# ESP32.net
KiCad netlist of a schematic drawn in EAGLE
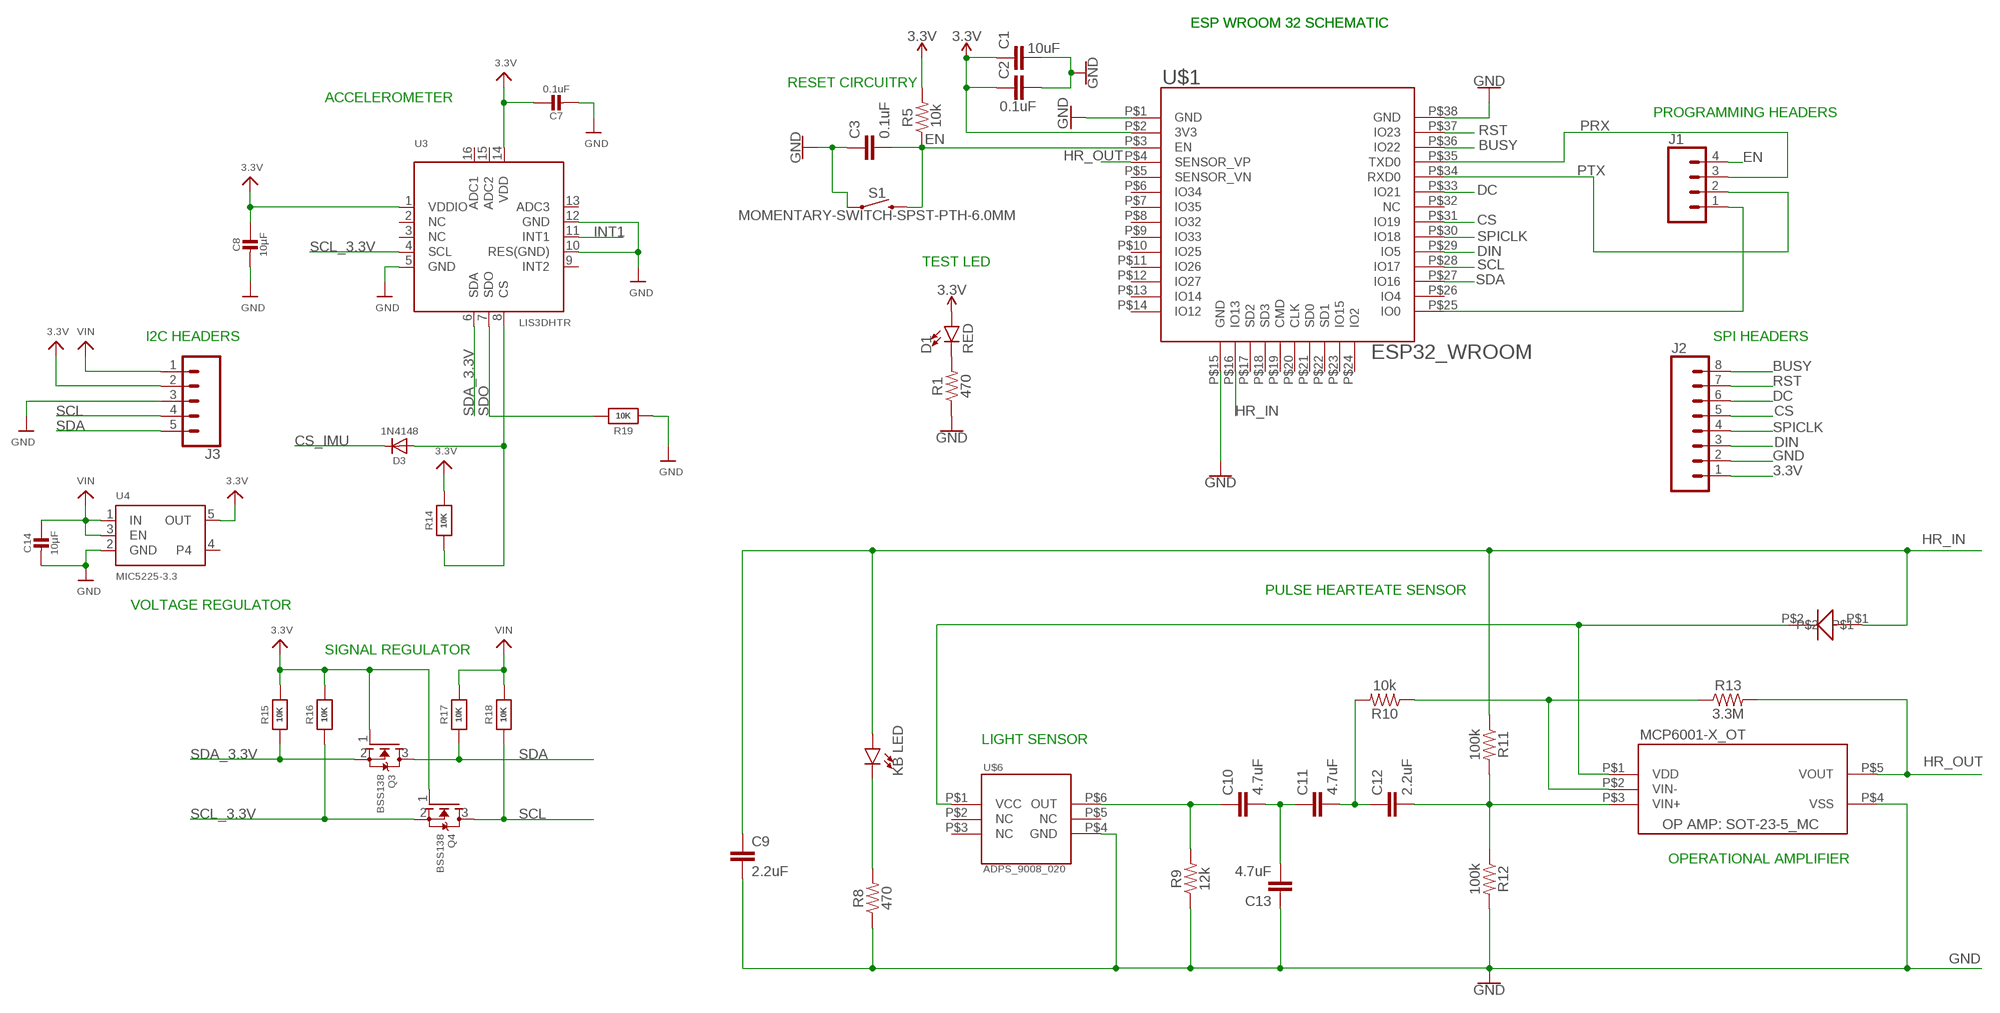
[diagram p0: schematic, sheet 1]

(export (version "E")
  (design (tool "Eeschema 10.0.6"))
  (components
    (comp (ref "C1")
      (value "10uF")
      (footprint "eagle-import:0603")
      (libsource (lib "eagle-import") (part "10UF-0603-6.3V-20%"))
    )
    (comp (ref "C2")
      (value "0.1uF")
      (footprint "eagle-import:0603")
      (libsource (lib "eagle-import") (part "0.1UF-0603-25V-(+80/-20%)"))
    )
    (comp (ref "C3")
      (value "0.1uF")
      (footprint "eagle-import:0603")
      (libsource (lib "eagle-import") (part "0.1UF-0603-25V-(+80/-20%)"))
    )
    (comp (ref "C7")
      (value "0.1uF")
      (footprint "eagle-import:_0603MP")
      (libsource (lib "eagle-import") (part "CAP_CERAMIC_0603MP"))
    )
    (comp (ref "C8")
      (value "10µF")
      (footprint "eagle-import:_0603")
      (libsource (lib "eagle-import") (part "CAP_CERAMIC_0603"))
    )
    (comp (ref "C9")
      (value "2.2uF")
      (footprint "eagle-import:0603")
      (libsource (lib "eagle-import") (part "2.2UF-0603-10V-20%"))
    )
    (comp (ref "C10")
      (value "4.7uF")
      (footprint "eagle-import:0603")
      (libsource (lib "eagle-import") (part "4.7UF0603"))
    )
    (comp (ref "C11")
      (value "4.7uF")
      (footprint "eagle-import:0603")
      (libsource (lib "eagle-import") (part "4.7UF0603"))
    )
    (comp (ref "C12")
      (value "2.2uF")
      (footprint "eagle-import:0603")
      (libsource (lib "eagle-import") (part "2.2UF-0603-10V-20%"))
    )
    (comp (ref "C13")
      (value "4.7uF")
      (footprint "eagle-import:0603")
      (libsource (lib "eagle-import") (part "4.7UF0603"))
    )
    (comp (ref "C14")
      (value "10µF")
      (footprint "eagle-import:_0603")
      (libsource (lib "eagle-import") (part "CAP_CERAMIC_0603"))
    )
    (comp (ref "D1")
      (value "RED")
      (footprint "eagle-import:LED-0603")
      (libsource (lib "eagle-import") (part "LED-RED0603"))
    )
    (comp (ref "D3")
      (value "1N4148")
      (footprint "eagle-import:SOD-323")
      (libsource (lib "eagle-import") (part "DIODESOD-323"))
    )
    (comp (ref "J1")
      (value "CONN_04")
      (footprint "eagle-import:1X04")
      (libsource (lib "eagle-import") (part "CONN_04"))
    )
    (comp (ref "J2")
      (value "CONN_08\"")
      (footprint "eagle-import:1X08")
      (libsource (lib "eagle-import") (part "CONN_08{dblquote}"))
    )
    (comp (ref "J3")
      (value "CONN_05")
      (footprint "eagle-import:1X05")
      (libsource (lib "eagle-import") (part "CONN_05"))
    )
    (comp (ref "Q3")
      (value "BSS138")
      (footprint "eagle-import:SOT23-WIDE")
      (libsource (lib "eagle-import") (part "MOSFET-NWIDE"))
    )
    (comp (ref "Q4")
      (value "BSS138")
      (footprint "eagle-import:SOT23-WIDE")
      (libsource (lib "eagle-import") (part "MOSFET-NWIDE"))
    )
    (comp (ref "R1")
      (value "470")
      (footprint "eagle-import:0603")
      (libsource (lib "eagle-import") (part "RESISTOR0603"))
    )
    (comp (ref "R5")
      (value "10k")
      (footprint "eagle-import:0603")
      (libsource (lib "eagle-import") (part "RESISTOR0603"))
    )
    (comp (ref "R8")
      (value "470")
      (footprint "eagle-import:0603")
      (libsource (lib "eagle-import") (part "RESISTOR0603"))
    )
    (comp (ref "R9")
      (value "12k")
      (footprint "eagle-import:0603")
      (libsource (lib "eagle-import") (part "RESISTOR0603"))
    )
    (comp (ref "R10")
      (value "10k")
      (footprint "eagle-import:0603")
      (libsource (lib "eagle-import") (part "RESISTOR0603"))
    )
    (comp (ref "R11")
      (value "100k")
      (footprint "eagle-import:0603")
      (libsource (lib "eagle-import") (part "RESISTOR0603"))
    )
    (comp (ref "R12")
      (value "100k")
      (footprint "eagle-import:0603")
      (libsource (lib "eagle-import") (part "RESISTOR0603"))
    )
    (comp (ref "R13")
      (value "3.3M")
      (footprint "eagle-import:0603")
      (libsource (lib "eagle-import") (part "RESISTOR0603"))
    )
    (comp (ref "R14")
      (value "10K")
      (footprint "eagle-import:_0603")
      (libsource (lib "eagle-import") (part "RESISTOR_0603"))
    )
    (comp (ref "R15")
      (value "10K")
      (footprint "eagle-import:_0603")
      (libsource (lib "eagle-import") (part "RESISTOR_0603"))
    )
    (comp (ref "R16")
      (value "10K")
      (footprint "eagle-import:_0603")
      (libsource (lib "eagle-import") (part "RESISTOR_0603"))
    )
    (comp (ref "R17")
      (value "10K")
      (footprint "eagle-import:_0603")
      (libsource (lib "eagle-import") (part "RESISTOR_0603"))
    )
    (comp (ref "R18")
      (value "10K")
      (footprint "eagle-import:_0603")
      (libsource (lib "eagle-import") (part "RESISTOR_0603"))
    )
    (comp (ref "R19")
      (value "10K")
      (footprint "eagle-import:_0603")
      (libsource (lib "eagle-import") (part "RESISTOR_0603"))
    )
    (comp (ref "S1")
      (value "MOMENTARY-SWITCH-SPST-PTH-6.0MM")
      (footprint "eagle-import:TACTILE_SWITCH_PTH_6.0MM")
      (libsource (lib "eagle-import") (part "MOMENTARY-SWITCH-SPST-PTH-6.0MM"))
    )
    (comp (ref "U$1")
      (value "ESP32_WROOM")
      (footprint "eagle-import:ESP32_FP")
      (libsource (lib "eagle-import") (part "ESP32_WROOM"))
    )
    (comp (ref "U$5")
      (value "MCP6001-X_SOT-23-5")
      (footprint "eagle-import:SOT-23-5")
      (libsource (lib "eagle-import") (part "MCP6001-X_SOT-23-5"))
    )
    (comp (ref "U$6")
      (value "ADPS_9008_020")
      (footprint "eagle-import:ADPS_FP")
      (libsource (lib "eagle-import") (part "ADPS_9008_020"))
    )
    (comp (ref "U$7")
      (value "KB_REVMNT_LED")
      (footprint "eagle-import:REVMNT_LED_FP")
      (libsource (lib "eagle-import") (part "KB_REVMNT_LED"))
    )
    (comp (ref "U$8")
      (value "DI0603")
      (footprint "eagle-import:DIODE0603")
      (libsource (lib "eagle-import") (part "DI0603"))
    )
    (comp (ref "U3")
      (value "LIS3DHTR")
      (footprint "eagle-import:LGA16_3X3MM")
      (libsource (lib "eagle-import") (part "ACCEL_LIS3DHTR"))
    )
    (comp (ref "U4")
      (value "MIC5225-3.3")
      (footprint "eagle-import:SOT23-5")
      (libsource (lib "eagle-import") (part "VREG_SOT23-5"))
    )
  )
  (nets
    (net (code "1") (name "/BUSY") (class "Default")
      (node (ref "J2") (pin "8") (pinfunction "8_8") (pintype "passive"))
      (node (ref "U$1") (pin "P$36") (pinfunction "IO22_P$36") (pintype "bidirectional"))
    )
    (net (code "2") (name "/CS") (class "Default")
      (node (ref "J2") (pin "5") (pinfunction "5_5") (pintype "passive"))
      (node (ref "U$1") (pin "P$31") (pinfunction "IO19_P$31") (pintype "bidirectional"))
    )
    (net (code "3") (name "/CS_IMU") (class "Default")
      (node (ref "D3") (pin "C") (pinfunction "C_C") (pintype "passive"))
    )
    (net (code "4") (name "/DC") (class "Default")
      (node (ref "J2") (pin "6") (pinfunction "6_6") (pintype "passive"))
      (node (ref "U$1") (pin "P$33") (pinfunction "IO21_P$33") (pintype "bidirectional"))
    )
    (net (code "5") (name "/DIN") (class "Default")
      (node (ref "J2") (pin "3") (pinfunction "3_3") (pintype "passive"))
      (node (ref "U$1") (pin "P$29") (pinfunction "IO5_P$29") (pintype "bidirectional"))
    )
    (net (code "6") (name "/EN") (class "Default")
      (node (ref "C3") (pin "2") (pinfunction "2_2") (pintype "passive"))
      (node (ref "J1") (pin "4") (pinfunction "4_4") (pintype "passive"))
      (node (ref "R5") (pin "1") (pinfunction "1_1") (pintype "passive"))
      (node (ref "S1") (pin "3") (pinfunction "2_3") (pintype "passive"))
      (node (ref "U$1") (pin "P$3") (pinfunction "EN_P$3") (pintype "input"))
    )
    (net (code "7") (name "/HR_IN") (class "Default")
      (node (ref "C9") (pin "1") (pinfunction "1_1") (pintype "passive"))
      (node (ref "R11") (pin "1") (pinfunction "1_1") (pintype "passive"))
      (node (ref "U$1") (pin "P$16") (pinfunction "IO13_P$16") (pintype "bidirectional"))
      (node (ref "U$7") (pin "P$1") (pinfunction "A_P$1") (pintype "passive"))
      (node (ref "U$8") (pin "P$1") (pinfunction "P$2_P$1") (pintype "bidirectional"))
    )
    (net (code "8") (name "/HR_OUT") (class "Default")
      (node (ref "R13") (pin "2") (pinfunction "2_2") (pintype "passive"))
      (node (ref "U$1") (pin "P$4") (pinfunction "SENSOR_VP_P$4") (pintype "input"))
      (node (ref "U$5") (pin "P$5") (pinfunction "VOUT_P$5") (pintype "output"))
    )
    (net (code "9") (name "/INT1") (class "Default")
      (node (ref "U3") (pin "11") (pinfunction "INT1_11") (pintype "output"))
    )
    (net (code "10") (name "/PRX") (class "Default")
      (node (ref "J1") (pin "3") (pinfunction "3_3") (pintype "passive"))
      (node (ref "U$1") (pin "P$35") (pinfunction "TXD0_P$35") (pintype "bidirectional"))
    )
    (net (code "11") (name "/PTX") (class "Default")
      (node (ref "J1") (pin "2") (pinfunction "2_2") (pintype "passive"))
      (node (ref "U$1") (pin "P$34") (pinfunction "RXD0_P$34") (pintype "bidirectional"))
    )
    (net (code "12") (name "/RST") (class "Default")
      (node (ref "J2") (pin "7") (pinfunction "7_7") (pintype "passive"))
      (node (ref "U$1") (pin "P$37") (pinfunction "IO23_P$37") (pintype "bidirectional"))
    )
    (net (code "13") (name "/SCL") (class "Default")
      (node (ref "J3") (pin "4") (pinfunction "4_4") (pintype "passive"))
      (node (ref "Q4") (pin "3") (pinfunction "D_3") (pintype "bidirectional"))
      (node (ref "R18") (pin "1") (pinfunction "1_1") (pintype "passive"))
      (node (ref "U$1") (pin "P$28") (pinfunction "IO17_P$28") (pintype "bidirectional"))
    )
    (net (code "14") (name "/SCL_3.3V") (class "Default")
      (node (ref "Q4") (pin "2") (pinfunction "S_2") (pintype "bidirectional"))
      (node (ref "R16") (pin "1") (pinfunction "1_1") (pintype "passive"))
      (node (ref "U3") (pin "4") (pinfunction "SCL_4") (pintype "bidirectional"))
    )
    (net (code "15") (name "/SDA") (class "Default")
      (node (ref "J3") (pin "5") (pinfunction "5_5") (pintype "passive"))
      (node (ref "Q3") (pin "3") (pinfunction "D_3") (pintype "bidirectional"))
      (node (ref "R17") (pin "1") (pinfunction "1_1") (pintype "passive"))
      (node (ref "U$1") (pin "P$27") (pinfunction "IO16_P$27") (pintype "bidirectional"))
    )
    (net (code "16") (name "/SDA_3.3V") (class "Default")
      (node (ref "Q3") (pin "2") (pinfunction "S_2") (pintype "bidirectional"))
      (node (ref "R15") (pin "1") (pinfunction "1_1") (pintype "passive"))
      (node (ref "U3") (pin "6") (pinfunction "SDA_6") (pintype "bidirectional"))
    )
    (net (code "17") (name "/SDO") (class "Default")
      (node (ref "R19") (pin "2") (pinfunction "2_2") (pintype "passive"))
      (node (ref "U3") (pin "7") (pinfunction "SDO_7") (pintype "bidirectional"))
    )
    (net (code "18") (name "/SPICLK") (class "Default")
      (node (ref "J2") (pin "4") (pinfunction "4_4") (pintype "passive"))
      (node (ref "U$1") (pin "P$30") (pinfunction "IO18_P$30") (pintype "bidirectional"))
    )
    (net (code "19") (name "3.3V") (class "Default")
      (node (ref "C1") (pin "1") (pinfunction "1_1") (pintype "passive"))
      (node (ref "C2") (pin "1") (pinfunction "1_1") (pintype "passive"))
      (node (ref "C7") (pin "1") (pinfunction "1_1") (pintype "passive"))
      (node (ref "C8") (pin "1") (pinfunction "1_1") (pintype "passive"))
      (node (ref "D1") (pin "A") (pinfunction "A_A") (pintype "passive"))
      (node (ref "J2") (pin "1") (pinfunction "1_1") (pintype "passive"))
      (node (ref "J3") (pin "2") (pinfunction "2_2") (pintype "passive"))
      (node (ref "Q3") (pin "1") (pinfunction "G_1") (pintype "bidirectional"))
      (node (ref "Q4") (pin "1") (pinfunction "G_1") (pintype "bidirectional"))
      (node (ref "R14") (pin "2") (pinfunction "2_2") (pintype "passive"))
      (node (ref "R15") (pin "2") (pinfunction "2_2") (pintype "passive"))
      (node (ref "R16") (pin "2") (pinfunction "2_2") (pintype "passive"))
      (node (ref "R5") (pin "2") (pinfunction "2_2") (pintype "passive"))
      (node (ref "U$1") (pin "P$2") (pinfunction "3V3_P$2") (pintype "power_in"))
      (node (ref "U3") (pin "1") (pinfunction "VDDIO_1") (pintype "power_in"))
      (node (ref "U3") (pin "14") (pinfunction "VDD_14") (pintype "power_in"))
      (node (ref "U4") (pin "5") (pinfunction "OUT_5") (pintype "power_in"))
    )
    (net (code "20") (name "GND") (class "Default")
      (node (ref "C1") (pin "2") (pinfunction "2_2") (pintype "passive"))
      (node (ref "C13") (pin "1") (pinfunction "1_1") (pintype "passive"))
      (node (ref "C14") (pin "2") (pinfunction "2_2") (pintype "passive"))
      (node (ref "C2") (pin "2") (pinfunction "2_2") (pintype "passive"))
      (node (ref "C3") (pin "1") (pinfunction "1_1") (pintype "passive"))
      (node (ref "C7") (pin "2") (pinfunction "2_2") (pintype "passive"))
      (node (ref "C8") (pin "2") (pinfunction "2_2") (pintype "passive"))
      (node (ref "C9") (pin "2") (pinfunction "2_2") (pintype "passive"))
      (node (ref "J2") (pin "2") (pinfunction "2_2") (pintype "passive"))
      (node (ref "J3") (pin "3") (pinfunction "3_3") (pintype "passive"))
      (node (ref "R1") (pin "1") (pinfunction "1_1") (pintype "passive"))
      (node (ref "R12") (pin "2") (pinfunction "2_2") (pintype "passive"))
      (node (ref "R19") (pin "1") (pinfunction "1_1") (pintype "passive"))
      (node (ref "R8") (pin "1") (pinfunction "1_1") (pintype "passive"))
      (node (ref "R9") (pin "1") (pinfunction "1_1") (pintype "passive"))
      (node (ref "S1") (pin "1") (pinfunction "1_1") (pintype "passive"))
      (node (ref "U$1") (pin "P$1") (pinfunction "GND_P$1") (pintype "power_in"))
      (node (ref "U$1") (pin "P$15") (pinfunction "GND_P$15") (pintype "power_in"))
      (node (ref "U$1") (pin "P$38") (pinfunction "GND_P$38") (pintype "power_in"))
      (node (ref "U$5") (pin "P$4") (pinfunction "VSS_P$4") (pintype "power_in"))
      (node (ref "U$6") (pin "P$4") (pinfunction "GND_P$4") (pintype "power_in"))
      (node (ref "U3") (pin "10") (pinfunction "RES(GND)_10") (pintype "bidirectional"))
      (node (ref "U3") (pin "12") (pinfunction "GND_12") (pintype "power_in"))
      (node (ref "U3") (pin "5") (pinfunction "GND_5") (pintype "power_in"))
      (node (ref "U4") (pin "2") (pinfunction "GND_2") (pintype "power_in"))
    )
    (net (code "21") (name "Net-(C10-Pad2)") (class "Default")
      (node (ref "C10") (pin "2") (pinfunction "2_2") (pintype "passive"))
      (node (ref "C11") (pin "1") (pinfunction "1_1") (pintype "passive"))
      (node (ref "C13") (pin "2") (pinfunction "2_2") (pintype "passive"))
    )
    (net (code "22") (name "Net-(C11-Pad2)") (class "Default")
      (node (ref "C11") (pin "2") (pinfunction "2_2") (pintype "passive"))
      (node (ref "C12") (pin "1") (pinfunction "1_1") (pintype "passive"))
      (node (ref "R10") (pin "2") (pinfunction "2_2") (pintype "passive"))
    )
    (net (code "23") (name "Net-(D1-PadC)") (class "Default")
      (node (ref "D1") (pin "C") (pinfunction "C_C") (pintype "passive"))
      (node (ref "R1") (pin "2") (pinfunction "2_2") (pintype "passive"))
    )
    (net (code "24") (name "Net-(U$1-IO0)") (class "Default")
      (node (ref "J1") (pin "1") (pinfunction "1_1") (pintype "passive"))
      (node (ref "U$1") (pin "P$25") (pinfunction "IO0_P$25") (pintype "bidirectional"))
    )
    (net (code "25") (name "Net-(U$5-VDD)") (class "Default")
      (node (ref "U$5") (pin "P$1") (pinfunction "VDD_P$1") (pintype "power_in"))
      (node (ref "U$6") (pin "P$1") (pinfunction "VCC_P$1") (pintype "power_in"))
      (node (ref "U$8") (pin "P$2") (pinfunction "P$1_P$2") (pintype "bidirectional"))
    )
    (net (code "26") (name "Net-(U$5-VIN+)") (class "Default")
      (node (ref "C12") (pin "2") (pinfunction "2_2") (pintype "passive"))
      (node (ref "R11") (pin "2") (pinfunction "2_2") (pintype "passive"))
      (node (ref "R12") (pin "1") (pinfunction "1_1") (pintype "passive"))
      (node (ref "U$5") (pin "P$3") (pinfunction "VIN+_P$3") (pintype "input"))
    )
    (net (code "27") (name "Net-(U$5-VIN-)") (class "Default")
      (node (ref "R10") (pin "1") (pinfunction "1_1") (pintype "passive"))
      (node (ref "R13") (pin "1") (pinfunction "1_1") (pintype "passive"))
      (node (ref "U$5") (pin "P$2") (pinfunction "VIN-_P$2") (pintype "input"))
    )
    (net (code "28") (name "Net-(U$6-OUT)") (class "Default")
      (node (ref "C10") (pin "1") (pinfunction "1_1") (pintype "passive"))
      (node (ref "R9") (pin "2") (pinfunction "2_2") (pintype "passive"))
      (node (ref "U$6") (pin "P$6") (pinfunction "OUT_P$6") (pintype "output"))
    )
    (net (code "29") (name "Net-(U$7-C)") (class "Default")
      (node (ref "R8") (pin "2") (pinfunction "2_2") (pintype "passive"))
      (node (ref "U$7") (pin "P$2") (pinfunction "C_P$2") (pintype "passive"))
    )
    (net (code "30") (name "Net-(U3-CS)") (class "Default")
      (node (ref "D3") (pin "A") (pinfunction "A_A") (pintype "passive"))
      (node (ref "R14") (pin "1") (pinfunction "1_1") (pintype "passive"))
      (node (ref "U3") (pin "8") (pinfunction "CS_8") (pintype "input"))
    )
    (net (code "31") (name "VIN") (class "Default")
      (node (ref "C14") (pin "1") (pinfunction "1_1") (pintype "passive"))
      (node (ref "J3") (pin "1") (pinfunction "1_1") (pintype "passive"))
      (node (ref "R17") (pin "2") (pinfunction "2_2") (pintype "passive"))
      (node (ref "R18") (pin "2") (pinfunction "2_2") (pintype "passive"))
      (node (ref "U4") (pin "1") (pinfunction "IN_1") (pintype "power_in"))
      (node (ref "U4") (pin "3") (pinfunction "EN_3") (pintype "input"))
    )
    (net (code "32") (name "unconnected-(U$1-CLK-PadP$20)") (class "Default")
      (node (ref "U$1") (pin "P$20") (pinfunction "CLK_P$20") (pintype "bidirectional"))
    )
    (net (code "33") (name "unconnected-(U$1-CMD-PadP$19)") (class "Default")
      (node (ref "U$1") (pin "P$19") (pinfunction "CMD_P$19") (pintype "bidirectional"))
    )
    (net (code "34") (name "unconnected-(U$1-IO2-PadP$24)") (class "Default")
      (node (ref "U$1") (pin "P$24") (pinfunction "IO2_P$24") (pintype "bidirectional"))
    )
    (net (code "35") (name "unconnected-(U$1-IO4-PadP$26)") (class "Default")
      (node (ref "U$1") (pin "P$26") (pinfunction "IO4_P$26") (pintype "bidirectional"))
    )
    (net (code "36") (name "unconnected-(U$1-IO12-PadP$14)") (class "Default")
      (node (ref "U$1") (pin "P$14") (pinfunction "IO12_P$14") (pintype "bidirectional"))
    )
    (net (code "37") (name "unconnected-(U$1-IO14-PadP$13)") (class "Default")
      (node (ref "U$1") (pin "P$13") (pinfunction "IO14_P$13") (pintype "bidirectional"))
    )
    (net (code "38") (name "unconnected-(U$1-IO15-PadP$23)") (class "Default")
      (node (ref "U$1") (pin "P$23") (pinfunction "IO15_P$23") (pintype "bidirectional"))
    )
    (net (code "39") (name "unconnected-(U$1-IO25-PadP$10)") (class "Default")
      (node (ref "U$1") (pin "P$10") (pinfunction "IO25_P$10") (pintype "bidirectional"))
    )
    (net (code "40") (name "unconnected-(U$1-IO26-PadP$11)") (class "Default")
      (node (ref "U$1") (pin "P$11") (pinfunction "IO26_P$11") (pintype "bidirectional"))
    )
    (net (code "41") (name "unconnected-(U$1-IO27-PadP$12)") (class "Default")
      (node (ref "U$1") (pin "P$12") (pinfunction "IO27_P$12") (pintype "bidirectional"))
    )
    (net (code "42") (name "unconnected-(U$1-IO32-PadP$8)") (class "Default")
      (node (ref "U$1") (pin "P$8") (pinfunction "IO32_P$8") (pintype "bidirectional"))
    )
    (net (code "43") (name "unconnected-(U$1-IO33-PadP$9)") (class "Default")
      (node (ref "U$1") (pin "P$9") (pinfunction "IO33_P$9") (pintype "bidirectional"))
    )
    (net (code "44") (name "unconnected-(U$1-IO34-PadP$6)") (class "Default")
      (node (ref "U$1") (pin "P$6") (pinfunction "IO34_P$6") (pintype "bidirectional"))
    )
    (net (code "45") (name "unconnected-(U$1-IO35-PadP$7)") (class "Default")
      (node (ref "U$1") (pin "P$7") (pinfunction "IO35_P$7") (pintype "bidirectional"))
    )
    (net (code "46") (name "unconnected-(U$1-NC-PadP$32)") (class "Default")
      (node (ref "U$1") (pin "P$32") (pinfunction "NC_P$32") (pintype "no_connect"))
    )
    (net (code "47") (name "unconnected-(U$1-SD0-PadP$21)") (class "Default")
      (node (ref "U$1") (pin "P$21") (pinfunction "SD0_P$21") (pintype "bidirectional"))
    )
    (net (code "48") (name "unconnected-(U$1-SD1-PadP$22)") (class "Default")
      (node (ref "U$1") (pin "P$22") (pinfunction "SD1_P$22") (pintype "bidirectional"))
    )
    (net (code "49") (name "unconnected-(U$1-SD2-PadP$17)") (class "Default")
      (node (ref "U$1") (pin "P$17") (pinfunction "SD2_P$17") (pintype "bidirectional"))
    )
    (net (code "50") (name "unconnected-(U$1-SD3-PadP$18)") (class "Default")
      (node (ref "U$1") (pin "P$18") (pinfunction "SD3_P$18") (pintype "bidirectional"))
    )
    (net (code "51") (name "unconnected-(U$1-SENSOR_VN-PadP$5)") (class "Default")
      (node (ref "U$1") (pin "P$5") (pinfunction "SENSOR_VN_P$5") (pintype "input"))
    )
    (net (code "52") (name "unconnected-(U$6-NC-PadP$2)") (class "Default")
      (node (ref "U$6") (pin "P$2") (pinfunction "NC_P$2") (pintype "bidirectional"))
    )
    (net (code "53") (name "unconnected-(U$6-NC-PadP$3)") (class "Default")
      (node (ref "U$6") (pin "P$3") (pinfunction "NC_P$3") (pintype "bidirectional"))
    )
    (net (code "54") (name "unconnected-(U$6-NC-PadP$5)") (class "Default")
      (node (ref "U$6") (pin "P$5") (pinfunction "NC_P$5") (pintype "bidirectional"))
    )
    (net (code "55") (name "unconnected-(U3-ADC1-Pad16)") (class "Default")
      (node (ref "U3") (pin "16") (pinfunction "ADC1_16") (pintype "input"))
    )
    (net (code "56") (name "unconnected-(U3-ADC2-Pad15)") (class "Default")
      (node (ref "U3") (pin "15") (pinfunction "ADC2_15") (pintype "input"))
    )
    (net (code "57") (name "unconnected-(U3-ADC3-Pad13)") (class "Default")
      (node (ref "U3") (pin "13") (pinfunction "ADC3_13") (pintype "input"))
    )
    (net (code "58") (name "unconnected-(U3-INT2-Pad9)") (class "Default")
      (node (ref "U3") (pin "9") (pinfunction "INT2_9") (pintype "output"))
    )
    (net (code "59") (name "unconnected-(U3-NC-Pad2)") (class "Default")
      (node (ref "U3") (pin "2") (pinfunction "NC_2") (pintype "no_connect"))
    )
    (net (code "60") (name "unconnected-(U3-NC-Pad3)") (class "Default")
      (node (ref "U3") (pin "3") (pinfunction "NC_3") (pintype "no_connect"))
    )
    (net (code "61") (name "unconnected-(U4-P4-Pad4)") (class "Default")
      (node (ref "U4") (pin "4") (pinfunction "P4_4") (pintype "bidirectional"))
    )
  )
)
